# Sheet1.net
KiCad netlist of a schematic drawn in Altium Designer
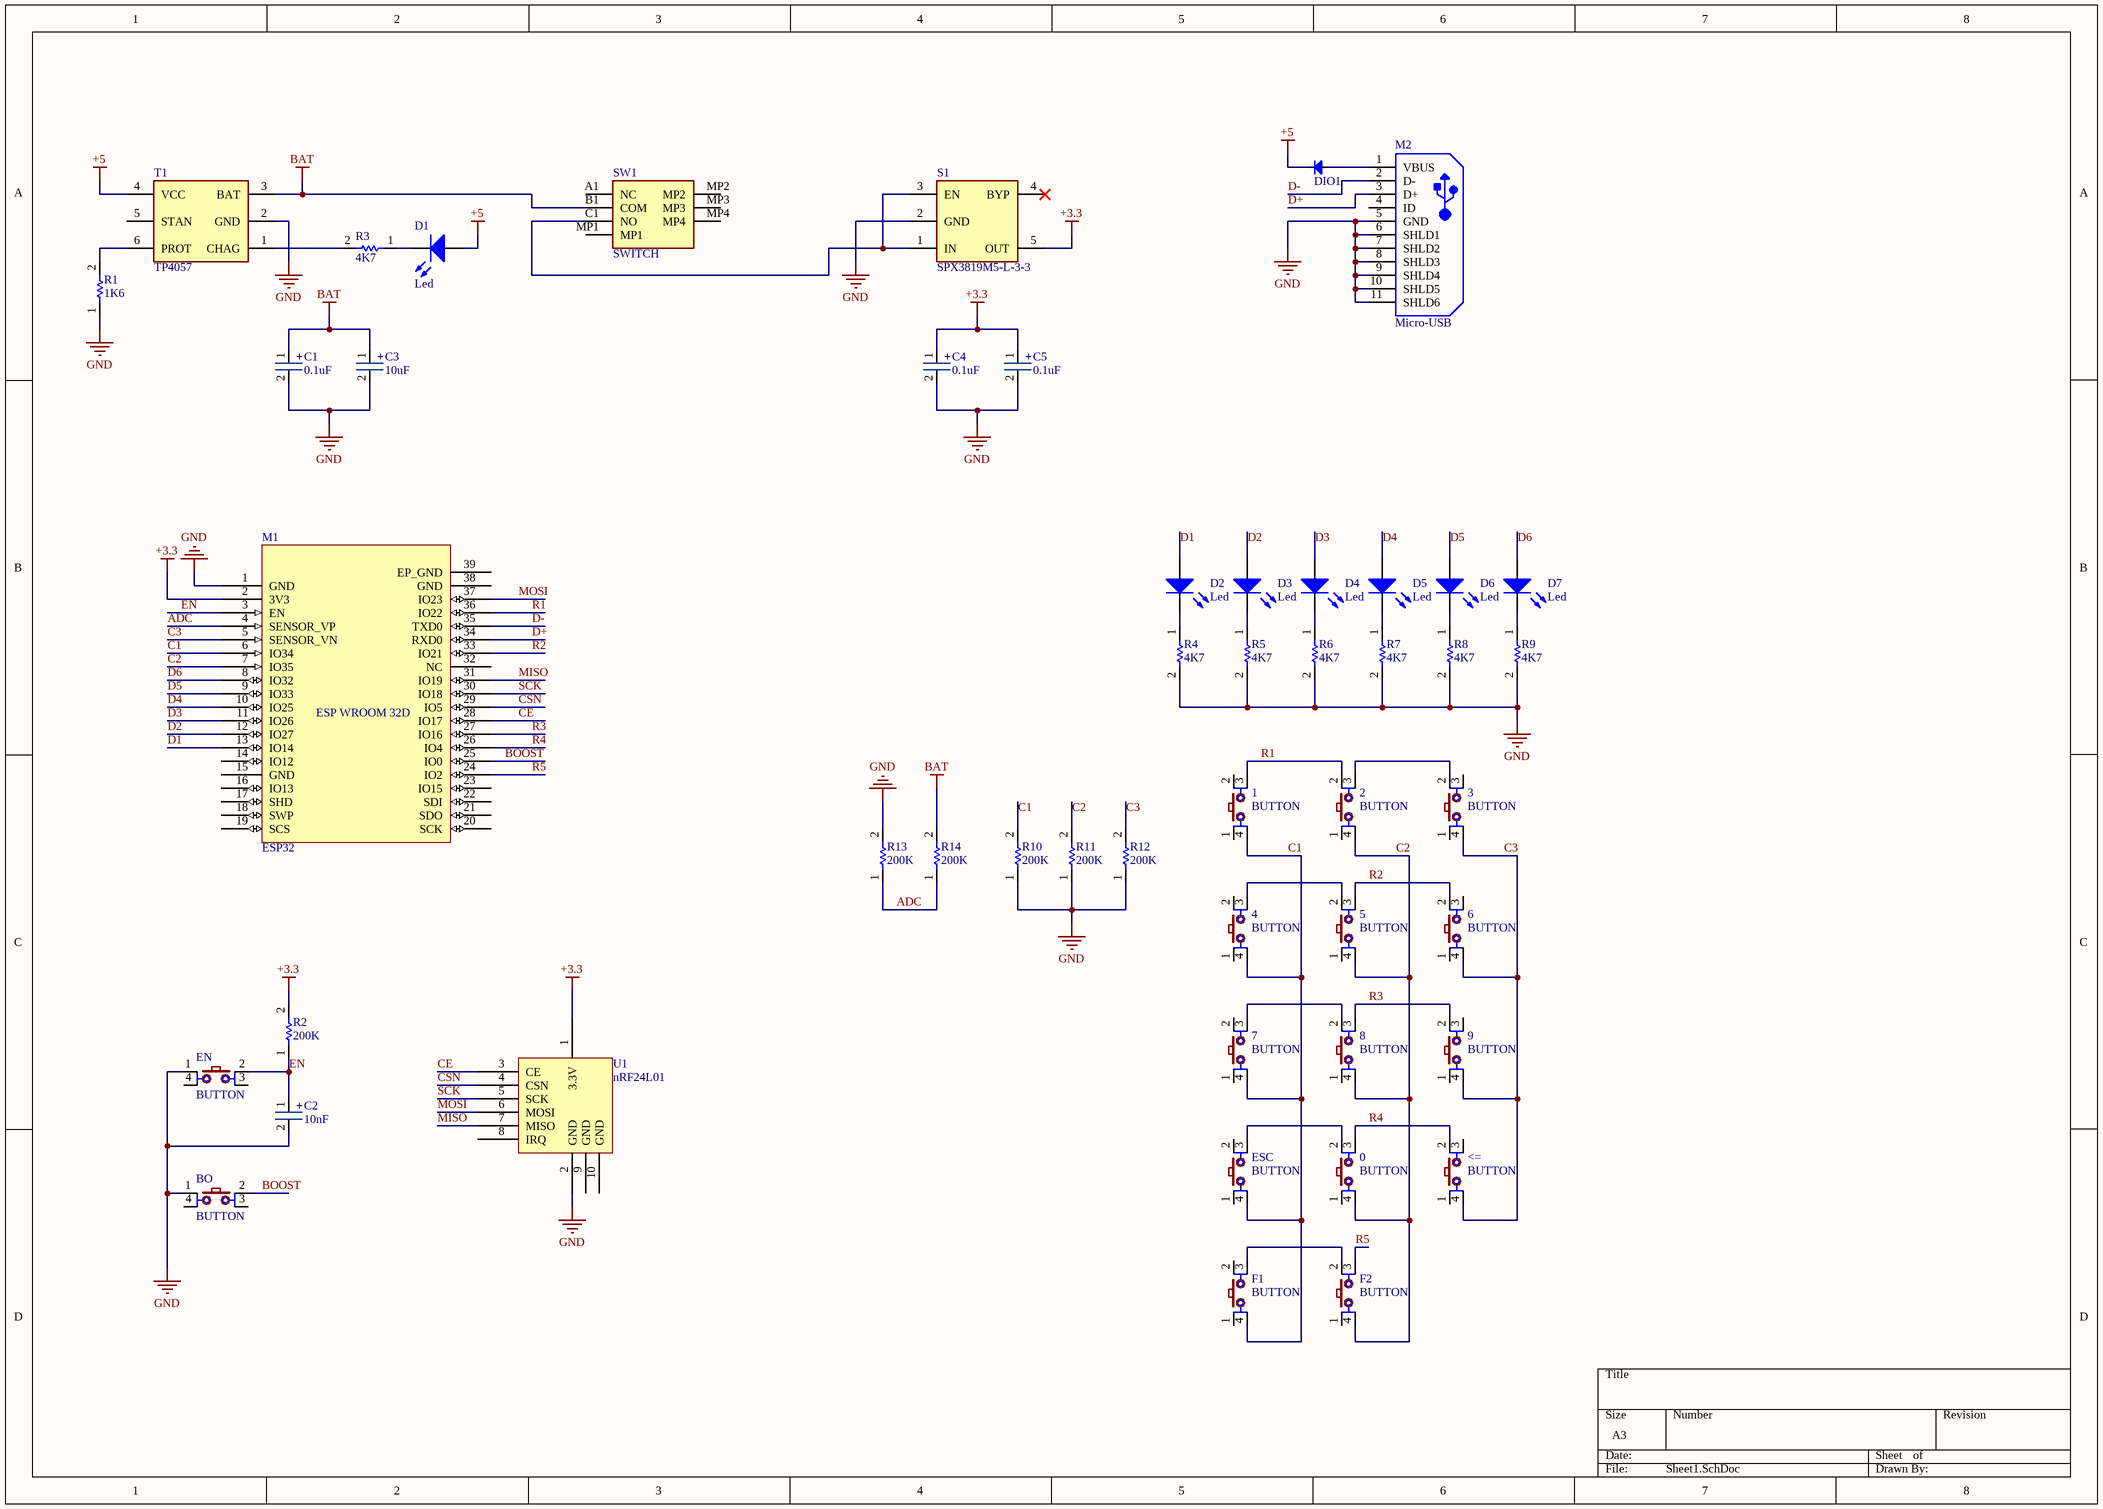
[diagram p0: Sheet1.SchDoc]

(export (version "E")
  (design (tool "Eeschema 10.0.6"))
  (components
    (comp (ref "0")
      (value "BUTTON")
      (footprint "BUTTON 4X4mm")
      (libsource (lib "Librarys") (part "BUTTON 4 PIN"))
    )
    (comp (ref "1")
      (value "BUTTON")
      (footprint "BUTTON 4X4mm")
      (libsource (lib "Librarys") (part "BUTTON 4 PIN"))
    )
    (comp (ref "2")
      (value "BUTTON")
      (footprint "BUTTON 4X4mm")
      (libsource (lib "Librarys") (part "BUTTON 4 PIN"))
    )
    (comp (ref "3")
      (value "BUTTON")
      (footprint "BUTTON 4X4mm")
      (libsource (lib "Librarys") (part "BUTTON 4 PIN"))
    )
    (comp (ref "4")
      (value "BUTTON")
      (footprint "BUTTON 4X4mm")
      (libsource (lib "Librarys") (part "BUTTON 4 PIN"))
    )
    (comp (ref "5")
      (value "BUTTON")
      (footprint "BUTTON 4X4mm")
      (libsource (lib "Librarys") (part "BUTTON 4 PIN"))
    )
    (comp (ref "6")
      (value "BUTTON")
      (footprint "BUTTON 4X4mm")
      (libsource (lib "Librarys") (part "BUTTON 4 PIN"))
    )
    (comp (ref "7")
      (value "BUTTON")
      (footprint "BUTTON 4X4mm")
      (libsource (lib "Librarys") (part "BUTTON 4 PIN"))
    )
    (comp (ref "8")
      (value "BUTTON")
      (footprint "BUTTON 4X4mm")
      (libsource (lib "Librarys") (part "BUTTON 4 PIN"))
    )
    (comp (ref "9")
      (value "BUTTON")
      (footprint "BUTTON 4X4mm")
      (libsource (lib "Librarys") (part "BUTTON 4 PIN"))
    )
    (comp (ref "<=")
      (value "BUTTON")
      (footprint "BUTTON 4X4mm")
      (libsource (lib "Librarys") (part "BUTTON 4 PIN"))
    )
    (comp (ref "BO")
      (value "BUTTON")
      (footprint "BUTTON 3x4mm 4PIN")
      (libsource (lib "Librarys") (part "BUTTON 4 PIN"))
    )
    (comp (ref "C1")
      (value "0.1uF")
      (footprint "Cap_0603_A")
      (description "General Purpose Ceramic Capacitor, 0603, 1nF, 10%, X7R, 15%, 50V")
      (fields (field (name "VOLTAGE") "50V") (field (name "TOLERANCE") "10%"))
      (libsource (lib "ResCapTransDio") (part "Capacitor"))
    )
    (comp (ref "C2")
      (value "10nF")
      (footprint "Cap_0603_A")
      (description "General Purpose Ceramic Capacitor, 0603, 1nF, 10%, X7R, 15%, 50V")
      (fields (field (name "VOLTAGE") "50V") (field (name "TOLERANCE") "10%"))
      (libsource (lib "ResCapTransDio") (part "Capacitor"))
    )
    (comp (ref "C3")
      (value "10uF")
      (footprint "Cap_0603_A")
      (description "General Purpose Ceramic Capacitor, 0603, 1nF, 10%, X7R, 15%, 50V")
      (fields (field (name "VOLTAGE") "50V") (field (name "TOLERANCE") "10%"))
      (libsource (lib "ResCapTransDio") (part "Capacitor"))
    )
    (comp (ref "C4")
      (value "0.1uF")
      (footprint "Cap_0603_A")
      (description "General Purpose Ceramic Capacitor, 0603, 1nF, 10%, X7R, 15%, 50V")
      (fields (field (name "VOLTAGE") "50V") (field (name "TOLERANCE") "10%"))
      (libsource (lib "ResCapTransDio") (part "Capacitor"))
    )
    (comp (ref "C5")
      (value "0.1uF")
      (footprint "Cap_0603_A")
      (description "General Purpose Ceramic Capacitor, 0603, 1nF, 10%, X7R, 15%, 50V")
      (fields (field (name "VOLTAGE") "50V") (field (name "TOLERANCE") "10%"))
      (libsource (lib "ResCapTransDio") (part "Capacitor"))
    )
    (comp (ref "D1") (value "Led") (footprint "LED 0603") (libsource (lib "ResCapTransDio") (part "Led")))
    (comp (ref "D2") (value "Led") (footprint "LED 0603") (libsource (lib "ResCapTransDio") (part "Led")))
    (comp (ref "D3") (value "Led") (footprint "LED 0603") (libsource (lib "ResCapTransDio") (part "Led")))
    (comp (ref "D4") (value "Led") (footprint "LED 0603") (libsource (lib "ResCapTransDio") (part "Led")))
    (comp (ref "D5") (value "Led") (footprint "LED 0603") (libsource (lib "ResCapTransDio") (part "Led")))
    (comp (ref "D6") (value "Led") (footprint "LED 0603") (libsource (lib "ResCapTransDio") (part "Led")))
    (comp (ref "D7") (value "Led") (footprint "LED 0603") (libsource (lib "ResCapTransDio") (part "Led")))
    (comp (ref "DIO1")
      (value "Diode SMD")
      (footprint "DIO-SMD-123")
      (description "Default Diode")
      (fields (field (name "PUBLISHER") "Altium Limited"))
      (libsource (lib "TechMT.VN_Lib_Project v2") (part "Diode SMD"))
    )
    (comp (ref "EN")
      (value "BUTTON")
      (footprint "BUTTON 3x4mm 4PIN")
      (libsource (lib "Librarys") (part "BUTTON 4 PIN"))
    )
    (comp (ref "ESC")
      (value "BUTTON")
      (footprint "BUTTON 4X4mm")
      (libsource (lib "Librarys") (part "BUTTON 4 PIN"))
    )
    (comp (ref "F1")
      (value "BUTTON")
      (footprint "BUTTON 4X4mm")
      (libsource (lib "Librarys") (part "BUTTON 4 PIN"))
    )
    (comp (ref "F2")
      (value "BUTTON")
      (footprint "BUTTON 4X4mm")
      (libsource (lib "Librarys") (part "BUTTON 4 PIN"))
    )
    (comp (ref "M1")
      (value "ESP32")
      (footprint "ESP32-WROOM-32D")
      (libsource (lib "ESP-WROOM-32D") (part "ESP32"))
    )
    (comp (ref "M2")
      (value "Micro-USB")
      (footprint "2.0 5 PIN SMD")
      (libsource (lib "Librarys") (part "Micro-USB"))
    )
    (comp (ref "R1")
      (value "1K6")
      (footprint "Res_0603")
      (libsource (lib "ResCapTransDio") (part "Resistor"))
    )
    (comp (ref "R2")
      (value "200K")
      (footprint "Res_0603")
      (libsource (lib "ResCapTransDio") (part "Resistor"))
    )
    (comp (ref "R3")
      (value "4K7")
      (footprint "Res_0603")
      (libsource (lib "ResCapTransDio") (part "Resistor"))
    )
    (comp (ref "R4")
      (value "4K7")
      (footprint "Res_0603")
      (libsource (lib "ResCapTransDio") (part "Resistor"))
    )
    (comp (ref "R5")
      (value "4K7")
      (footprint "Res_0603")
      (libsource (lib "ResCapTransDio") (part "Resistor"))
    )
    (comp (ref "R6")
      (value "4K7")
      (footprint "Res_0603")
      (libsource (lib "ResCapTransDio") (part "Resistor"))
    )
    (comp (ref "R7")
      (value "4K7")
      (footprint "Res_0603")
      (libsource (lib "ResCapTransDio") (part "Resistor"))
    )
    (comp (ref "R8")
      (value "4K7")
      (footprint "Res_0603")
      (libsource (lib "ResCapTransDio") (part "Resistor"))
    )
    (comp (ref "R9")
      (value "4K7")
      (footprint "Res_0603")
      (libsource (lib "ResCapTransDio") (part "Resistor"))
    )
    (comp (ref "R10")
      (value "200K")
      (footprint "Res_0603")
      (libsource (lib "ResCapTransDio") (part "Resistor"))
    )
    (comp (ref "R11")
      (value "200K")
      (footprint "Res_0603")
      (libsource (lib "ResCapTransDio") (part "Resistor"))
    )
    (comp (ref "R12")
      (value "200K")
      (footprint "Res_0603")
      (libsource (lib "ResCapTransDio") (part "Resistor"))
    )
    (comp (ref "R13")
      (value "200K")
      (footprint "Res_0603")
      (libsource (lib "ResCapTransDio") (part "Resistor"))
    )
    (comp (ref "R14")
      (value "200K")
      (footprint "Res_0603")
      (libsource (lib "ResCapTransDio") (part "Resistor"))
    )
    (comp (ref "S1")
      (value "SPX3819M5-L-3-3")
      (footprint "FP-C04-091-OT-IPC_A")
      (description "Regulator 250mA")
      (libsource (lib "Regulator") (part "SPX3819M5-L-3-3"))
    )
    (comp (ref "SW1") (value "SWITCH") (footprint "MSK12C02") (libsource (lib "Librarys") (part "SWITCH")))
    (comp (ref "T1") (value "TP4057") (footprint "TP4057") (libsource (lib "Librarys") (part "TP4057")))
    (comp (ref "U1")
      (value "nRF24L01")
      (footprint "NRF24L01 + PA SMD")
      (libsource (lib "MODULEs") (part "nRF24L01"))
    )
  )
  (nets
    (net (code "1") (name "+3.3") (class "Default")
      (node (ref "C4") (pin "1") (pinfunction "1_1") (pintype "passive"))
      (node (ref "C5") (pin "1") (pinfunction "1_1") (pintype "passive"))
      (node (ref "M1") (pin "2") (pinfunction "3V3_2") (pintype "passive"))
      (node (ref "R2") (pin "2") (pinfunction "2_2") (pintype "passive"))
      (node (ref "S1") (pin "5") (pinfunction "OUT_5") (pintype "passive"))
      (node (ref "U1") (pin "1") (pinfunction "3.3V_1") (pintype "passive"))
    )
    (net (code "2") (name "+5") (class "Default")
      (node (ref "D1") (pin "1") (pinfunction "A_1") (pintype "passive"))
      (node (ref "DIO1") (pin "2") (pinfunction "K_2") (pintype "passive"))
      (node (ref "T1") (pin "4") (pinfunction "VCC_4") (pintype "power_in"))
    )
    (net (code "3") (name "/ADC") (class "Default")
      (node (ref "M1") (pin "4") (pinfunction "SENSOR_VP_4") (pintype "input"))
      (node (ref "R13") (pin "1") (pinfunction "1_1") (pintype "passive"))
      (node (ref "R14") (pin "1") (pinfunction "1_1") (pintype "passive"))
    )
    (net (code "4") (name "/BOOST") (class "Default")
      (node (ref "BO") (pin "2") (pinfunction "2_2") (pintype "passive"))
      (node (ref "M1") (pin "25") (pinfunction "IO0_25") (pintype "bidirectional"))
    )
    (net (code "5") (name "/C1") (class "Default")
      (node (ref "1") (pin "4") (pinfunction "4_4") (pintype "passive"))
      (node (ref "4") (pin "4") (pinfunction "4_4") (pintype "passive"))
      (node (ref "7") (pin "4") (pinfunction "4_4") (pintype "passive"))
      (node (ref "ESC") (pin "4") (pinfunction "4_4") (pintype "passive"))
      (node (ref "F1") (pin "4") (pinfunction "4_4") (pintype "passive"))
      (node (ref "M1") (pin "6") (pinfunction "IO34_6") (pintype "input"))
      (node (ref "R10") (pin "2") (pinfunction "2_2") (pintype "passive"))
    )
    (net (code "6") (name "/C2") (class "Default")
      (node (ref "0") (pin "4") (pinfunction "4_4") (pintype "passive"))
      (node (ref "2") (pin "4") (pinfunction "4_4") (pintype "passive"))
      (node (ref "5") (pin "4") (pinfunction "4_4") (pintype "passive"))
      (node (ref "8") (pin "4") (pinfunction "4_4") (pintype "passive"))
      (node (ref "F2") (pin "4") (pinfunction "4_4") (pintype "passive"))
      (node (ref "M1") (pin "7") (pinfunction "IO35_7") (pintype "input"))
      (node (ref "R11") (pin "2") (pinfunction "2_2") (pintype "passive"))
    )
    (net (code "7") (name "/C3") (class "Default")
      (node (ref "3") (pin "4") (pinfunction "4_4") (pintype "passive"))
      (node (ref "6") (pin "4") (pinfunction "4_4") (pintype "passive"))
      (node (ref "9") (pin "4") (pinfunction "4_4") (pintype "passive"))
      (node (ref "<=") (pin "4") (pinfunction "4_4") (pintype "passive"))
      (node (ref "M1") (pin "5") (pinfunction "SENSOR_VN_5") (pintype "input"))
      (node (ref "R12") (pin "2") (pinfunction "2_2") (pintype "passive"))
    )
    (net (code "8") (name "/CE") (class "Default")
      (node (ref "M1") (pin "28") (pinfunction "IO17_28") (pintype "bidirectional"))
      (node (ref "U1") (pin "3") (pinfunction "CE_3") (pintype "passive"))
    )
    (net (code "9") (name "/CSN") (class "Default")
      (node (ref "M1") (pin "29") (pinfunction "IO5_29") (pintype "bidirectional"))
      (node (ref "U1") (pin "4") (pinfunction "CSN_4") (pintype "passive"))
    )
    (net (code "10") (name "/D+") (class "Default")
      (node (ref "M1") (pin "34") (pinfunction "RXD0_34") (pintype "bidirectional"))
      (node (ref "M2") (pin "3") (pinfunction "D+_3") (pintype "passive"))
    )
    (net (code "11") (name "/D-") (class "Default")
      (node (ref "M1") (pin "35") (pinfunction "TXD0_35") (pintype "bidirectional"))
      (node (ref "M2") (pin "2") (pinfunction "D-_2") (pintype "passive"))
    )
    (net (code "12") (name "/D1") (class "Default")
      (node (ref "D2") (pin "1") (pinfunction "A_1") (pintype "passive"))
      (node (ref "M1") (pin "13") (pinfunction "IO14_13") (pintype "bidirectional"))
    )
    (net (code "13") (name "/D2") (class "Default")
      (node (ref "D3") (pin "1") (pinfunction "A_1") (pintype "passive"))
      (node (ref "M1") (pin "12") (pinfunction "IO27_12") (pintype "bidirectional"))
    )
    (net (code "14") (name "/D3") (class "Default")
      (node (ref "D4") (pin "1") (pinfunction "A_1") (pintype "passive"))
      (node (ref "M1") (pin "11") (pinfunction "IO26_11") (pintype "bidirectional"))
    )
    (net (code "15") (name "/D4") (class "Default")
      (node (ref "D5") (pin "1") (pinfunction "A_1") (pintype "passive"))
      (node (ref "M1") (pin "10") (pinfunction "IO25_10") (pintype "bidirectional"))
    )
    (net (code "16") (name "/D5") (class "Default")
      (node (ref "D6") (pin "1") (pinfunction "A_1") (pintype "passive"))
      (node (ref "M1") (pin "9") (pinfunction "IO33_9") (pintype "bidirectional"))
    )
    (net (code "17") (name "/D6") (class "Default")
      (node (ref "D7") (pin "1") (pinfunction "A_1") (pintype "passive"))
      (node (ref "M1") (pin "8") (pinfunction "IO32_8") (pintype "bidirectional"))
    )
    (net (code "18") (name "/EN") (class "Default")
      (node (ref "C2") (pin "1") (pinfunction "1_1") (pintype "passive"))
      (node (ref "EN") (pin "2") (pinfunction "2_2") (pintype "passive"))
      (node (ref "M1") (pin "3") (pinfunction "EN_3") (pintype "input"))
      (node (ref "R2") (pin "1") (pinfunction "1_1") (pintype "passive"))
    )
    (net (code "19") (name "/MISO") (class "Default")
      (node (ref "M1") (pin "31") (pinfunction "IO19_31") (pintype "bidirectional"))
      (node (ref "U1") (pin "7") (pinfunction "MISO_7") (pintype "passive"))
    )
    (net (code "20") (name "/MOSI") (class "Default")
      (node (ref "M1") (pin "37") (pinfunction "IO23_37") (pintype "bidirectional"))
      (node (ref "U1") (pin "6") (pinfunction "MOSI_6") (pintype "passive"))
    )
    (net (code "21") (name "/R1") (class "Default")
      (node (ref "1") (pin "3") (pinfunction "3_3") (pintype "passive"))
      (node (ref "2") (pin "2") (pinfunction "2_2") (pintype "passive"))
      (node (ref "M1") (pin "36") (pinfunction "IO22_36") (pintype "bidirectional"))
    )
    (net (code "22") (name "/R2") (class "Default")
      (node (ref "5") (pin "3") (pinfunction "3_3") (pintype "passive"))
      (node (ref "6") (pin "2") (pinfunction "2_2") (pintype "passive"))
      (node (ref "M1") (pin "33") (pinfunction "IO21_33") (pintype "bidirectional"))
    )
    (net (code "23") (name "/R3") (class "Default")
      (node (ref "8") (pin "3") (pinfunction "3_3") (pintype "passive"))
      (node (ref "9") (pin "2") (pinfunction "2_2") (pintype "passive"))
      (node (ref "M1") (pin "27") (pinfunction "IO16_27") (pintype "bidirectional"))
    )
    (net (code "24") (name "/R4") (class "Default")
      (node (ref "0") (pin "3") (pinfunction "3_3") (pintype "passive"))
      (node (ref "<=") (pin "2") (pinfunction "2_2") (pintype "passive"))
      (node (ref "M1") (pin "26") (pinfunction "IO4_26") (pintype "bidirectional"))
    )
    (net (code "25") (name "/R5") (class "Default")
      (node (ref "F2") (pin "3") (pinfunction "3_3") (pintype "passive"))
      (node (ref "M1") (pin "24") (pinfunction "IO2_24") (pintype "bidirectional"))
    )
    (net (code "26") (name "/SCK") (class "Default")
      (node (ref "M1") (pin "30") (pinfunction "IO18_30") (pintype "bidirectional"))
      (node (ref "U1") (pin "5") (pinfunction "SCK_5") (pintype "passive"))
    )
    (net (code "27") (name "BAT") (class "Default")
      (node (ref "C1") (pin "1") (pinfunction "1_1") (pintype "passive"))
      (node (ref "C3") (pin "1") (pinfunction "1_1") (pintype "passive"))
      (node (ref "R14") (pin "2") (pinfunction "2_2") (pintype "passive"))
      (node (ref "SW1") (pin "B1") (pinfunction "COM_B1") (pintype "passive"))
      (node (ref "T1") (pin "3") (pinfunction "BAT_3") (pintype "power_in"))
    )
    (net (code "28") (name "GND") (class "Default")
      (node (ref "BO") (pin "1") (pintype "passive"))
      (node (ref "C1") (pin "2") (pinfunction "2_2") (pintype "passive"))
      (node (ref "C2") (pin "2") (pinfunction "2_2") (pintype "passive"))
      (node (ref "C3") (pin "2") (pinfunction "2_2") (pintype "passive"))
      (node (ref "C4") (pin "2") (pinfunction "2_2") (pintype "passive"))
      (node (ref "C5") (pin "2") (pinfunction "2_2") (pintype "passive"))
      (node (ref "EN") (pin "1") (pintype "passive"))
      (node (ref "M1") (pin "1") (pinfunction "GND_1") (pintype "passive"))
      (node (ref "M2") (pin "10") (pinfunction "SHLD5_10") (pintype "passive"))
      (node (ref "M2") (pin "11") (pinfunction "SHLD6_11") (pintype "passive"))
      (node (ref "M2") (pin "5") (pinfunction "GND_5") (pintype "passive"))
      (node (ref "M2") (pin "6") (pinfunction "SHLD1_6") (pintype "passive"))
      (node (ref "M2") (pin "7") (pinfunction "SHLD2_7") (pintype "passive"))
      (node (ref "M2") (pin "8") (pinfunction "SHLD3_8") (pintype "passive"))
      (node (ref "M2") (pin "9") (pinfunction "SHLD4_9") (pintype "passive"))
      (node (ref "R1") (pin "1") (pinfunction "1_1") (pintype "passive"))
      (node (ref "R10") (pin "1") (pinfunction "1_1") (pintype "passive"))
      (node (ref "R11") (pin "1") (pinfunction "1_1") (pintype "passive"))
      (node (ref "R12") (pin "1") (pinfunction "1_1") (pintype "passive"))
      (node (ref "R13") (pin "2") (pinfunction "2_2") (pintype "passive"))
      (node (ref "R4") (pin "2") (pinfunction "2_2") (pintype "passive"))
      (node (ref "R5") (pin "2") (pinfunction "2_2") (pintype "passive"))
      (node (ref "R6") (pin "2") (pinfunction "2_2") (pintype "passive"))
      (node (ref "R7") (pin "2") (pinfunction "2_2") (pintype "passive"))
      (node (ref "R8") (pin "2") (pinfunction "2_2") (pintype "passive"))
      (node (ref "R9") (pin "2") (pinfunction "2_2") (pintype "passive"))
      (node (ref "S1") (pin "2") (pinfunction "GND_2") (pintype "passive"))
      (node (ref "T1") (pin "2") (pinfunction "GND_2") (pintype "passive"))
      (node (ref "U1") (pin "2") (pinfunction "GND_2") (pintype "passive"))
    )
    (net (code "29") (name "Net-(0-Pad2)") (class "Default")
      (node (ref "0") (pin "2") (pinfunction "2_2") (pintype "passive"))
      (node (ref "ESC") (pin "3") (pinfunction "3_3") (pintype "passive"))
    )
    (net (code "30") (name "Net-(2-Pad3)") (class "Default")
      (node (ref "2") (pin "3") (pinfunction "3_3") (pintype "passive"))
      (node (ref "3") (pin "2") (pinfunction "2_2") (pintype "passive"))
    )
    (net (code "31") (name "Net-(4-Pad3)") (class "Default")
      (node (ref "4") (pin "3") (pinfunction "3_3") (pintype "passive"))
      (node (ref "5") (pin "2") (pinfunction "2_2") (pintype "passive"))
    )
    (net (code "32") (name "Net-(7-Pad3)") (class "Default")
      (node (ref "7") (pin "3") (pinfunction "3_3") (pintype "passive"))
      (node (ref "8") (pin "2") (pinfunction "2_2") (pintype "passive"))
    )
    (net (code "33") (name "Net-(D1-K)") (class "Default")
      (node (ref "D1") (pin "2") (pinfunction "K_2") (pintype "passive"))
      (node (ref "R3") (pin "1") (pinfunction "1_1") (pintype "passive"))
    )
    (net (code "34") (name "Net-(D2-K)") (class "Default")
      (node (ref "D2") (pin "2") (pinfunction "K_2") (pintype "passive"))
      (node (ref "R4") (pin "1") (pinfunction "1_1") (pintype "passive"))
    )
    (net (code "35") (name "Net-(D3-K)") (class "Default")
      (node (ref "D3") (pin "2") (pinfunction "K_2") (pintype "passive"))
      (node (ref "R5") (pin "1") (pinfunction "1_1") (pintype "passive"))
    )
    (net (code "36") (name "Net-(D4-K)") (class "Default")
      (node (ref "D4") (pin "2") (pinfunction "K_2") (pintype "passive"))
      (node (ref "R6") (pin "1") (pinfunction "1_1") (pintype "passive"))
    )
    (net (code "37") (name "Net-(D5-K)") (class "Default")
      (node (ref "D5") (pin "2") (pinfunction "K_2") (pintype "passive"))
      (node (ref "R7") (pin "1") (pinfunction "1_1") (pintype "passive"))
    )
    (net (code "38") (name "Net-(D6-K)") (class "Default")
      (node (ref "D6") (pin "2") (pinfunction "K_2") (pintype "passive"))
      (node (ref "R8") (pin "1") (pinfunction "1_1") (pintype "passive"))
    )
    (net (code "39") (name "Net-(D7-K)") (class "Default")
      (node (ref "D7") (pin "2") (pinfunction "K_2") (pintype "passive"))
      (node (ref "R9") (pin "1") (pinfunction "1_1") (pintype "passive"))
    )
    (net (code "40") (name "Net-(DIO1-A)") (class "Default")
      (node (ref "DIO1") (pin "1") (pinfunction "A_1") (pintype "passive"))
      (node (ref "M2") (pin "1") (pinfunction "VBUS_1") (pintype "passive"))
    )
    (net (code "41") (name "Net-(F1-Pad3)") (class "Default")
      (node (ref "F1") (pin "3") (pinfunction "3_3") (pintype "passive"))
      (node (ref "F2") (pin "2") (pinfunction "2_2") (pintype "passive"))
    )
    (net (code "42") (name "Net-(S1-EN)") (class "Default")
      (node (ref "S1") (pin "1") (pinfunction "IN_1") (pintype "power_in"))
      (node (ref "S1") (pin "3") (pinfunction "EN_3") (pintype "power_in"))
      (node (ref "SW1") (pin "C1") (pinfunction "NO_C1") (pintype "passive"))
    )
    (net (code "43") (name "Net-(T1-CHAG)") (class "Default")
      (node (ref "R3") (pin "2") (pinfunction "2_2") (pintype "passive"))
      (node (ref "T1") (pin "1") (pinfunction "CHAG_1") (pintype "power_in"))
    )
    (net (code "44") (name "Net-(T1-PROT)") (class "Default")
      (node (ref "R1") (pin "2") (pinfunction "2_2") (pintype "passive"))
      (node (ref "T1") (pin "6") (pinfunction "PROT_6") (pintype "passive"))
    )
    (net (code "45") (name "unconnected-(0-Pad1)") (class "Default")
      (node (ref "0") (pin "1") (pintype "passive"))
    )
    (net (code "46") (name "unconnected-(1-Pad1)") (class "Default")
      (node (ref "1") (pin "1") (pintype "passive"))
    )
    (net (code "47") (name "unconnected-(1-Pad2)") (class "Default")
      (node (ref "1") (pin "2") (pinfunction "2_2") (pintype "passive"))
    )
    (net (code "48") (name "unconnected-(2-Pad1)") (class "Default")
      (node (ref "2") (pin "1") (pintype "passive"))
    )
    (net (code "49") (name "unconnected-(3-Pad1)") (class "Default")
      (node (ref "3") (pin "1") (pintype "passive"))
    )
    (net (code "50") (name "unconnected-(3-Pad3)") (class "Default")
      (node (ref "3") (pin "3") (pinfunction "3_3") (pintype "passive"))
    )
    (net (code "51") (name "unconnected-(4-Pad1)") (class "Default")
      (node (ref "4") (pin "1") (pintype "passive"))
    )
    (net (code "52") (name "unconnected-(4-Pad2)") (class "Default")
      (node (ref "4") (pin "2") (pinfunction "2_2") (pintype "passive"))
    )
    (net (code "53") (name "unconnected-(5-Pad1)") (class "Default")
      (node (ref "5") (pin "1") (pintype "passive"))
    )
    (net (code "54") (name "unconnected-(6-Pad1)") (class "Default")
      (node (ref "6") (pin "1") (pintype "passive"))
    )
    (net (code "55") (name "unconnected-(6-Pad3)") (class "Default")
      (node (ref "6") (pin "3") (pinfunction "3_3") (pintype "passive"))
    )
    (net (code "56") (name "unconnected-(7-Pad1)") (class "Default")
      (node (ref "7") (pin "1") (pintype "passive"))
    )
    (net (code "57") (name "unconnected-(7-Pad2)") (class "Default")
      (node (ref "7") (pin "2") (pinfunction "2_2") (pintype "passive"))
    )
    (net (code "58") (name "unconnected-(8-Pad1)") (class "Default")
      (node (ref "8") (pin "1") (pintype "passive"))
    )
    (net (code "59") (name "unconnected-(9-Pad1)") (class "Default")
      (node (ref "9") (pin "1") (pintype "passive"))
    )
    (net (code "60") (name "unconnected-(9-Pad3)") (class "Default")
      (node (ref "9") (pin "3") (pinfunction "3_3") (pintype "passive"))
    )
    (net (code "61") (name "unconnected-(<=-Pad1)") (class "Default")
      (node (ref "<=") (pin "1") (pintype "passive"))
    )
    (net (code "62") (name "unconnected-(<=-Pad3)") (class "Default")
      (node (ref "<=") (pin "3") (pinfunction "3_3") (pintype "passive"))
    )
    (net (code "63") (name "unconnected-(BO-Pad3)") (class "Default")
      (node (ref "BO") (pin "3") (pinfunction "3_3") (pintype "passive"))
    )
    (net (code "64") (name "unconnected-(BO-Pad4)") (class "Default")
      (node (ref "BO") (pin "4") (pinfunction "4_4") (pintype "passive"))
    )
    (net (code "65") (name "unconnected-(EN-Pad3)") (class "Default")
      (node (ref "EN") (pin "3") (pinfunction "3_3") (pintype "passive"))
    )
    (net (code "66") (name "unconnected-(EN-Pad4)") (class "Default")
      (node (ref "EN") (pin "4") (pinfunction "4_4") (pintype "passive"))
    )
    (net (code "67") (name "unconnected-(ESC-Pad1)") (class "Default")
      (node (ref "ESC") (pin "1") (pintype "passive"))
    )
    (net (code "68") (name "unconnected-(ESC-Pad2)") (class "Default")
      (node (ref "ESC") (pin "2") (pinfunction "2_2") (pintype "passive"))
    )
    (net (code "69") (name "unconnected-(F1-Pad1)") (class "Default")
      (node (ref "F1") (pin "1") (pintype "passive"))
    )
    (net (code "70") (name "unconnected-(F1-Pad2)") (class "Default")
      (node (ref "F1") (pin "2") (pinfunction "2_2") (pintype "passive"))
    )
    (net (code "71") (name "unconnected-(F2-Pad1)") (class "Default")
      (node (ref "F2") (pin "1") (pintype "passive"))
    )
    (net (code "72") (name "unconnected-(M1-EP_GND-Pad39)") (class "Default")
      (node (ref "M1") (pin "39") (pinfunction "EP_GND_39") (pintype "passive"))
    )
    (net (code "73") (name "unconnected-(M1-GND-Pad15)") (class "Default")
      (node (ref "M1") (pin "15") (pinfunction "GND_15") (pintype "passive"))
    )
    (net (code "74") (name "unconnected-(M1-GND-Pad38)") (class "Default")
      (node (ref "M1") (pin "38") (pinfunction "GND_38") (pintype "passive"))
    )
    (net (code "75") (name "unconnected-(M1-IO12-Pad14)") (class "Default")
      (node (ref "M1") (pin "14") (pinfunction "IO12_14") (pintype "bidirectional"))
    )
    (net (code "76") (name "unconnected-(M1-IO13-Pad16)") (class "Default")
      (node (ref "M1") (pin "16") (pinfunction "IO13_16") (pintype "bidirectional"))
    )
    (net (code "77") (name "unconnected-(M1-IO15-Pad23)") (class "Default")
      (node (ref "M1") (pin "23") (pinfunction "IO15_23") (pintype "bidirectional"))
    )
    (net (code "78") (name "unconnected-(M1-NC-Pad32)") (class "Default")
      (node (ref "M1") (pin "32") (pinfunction "NC_32") (pintype "passive"))
    )
    (net (code "79") (name "unconnected-(M1-SCK-Pad20)") (class "Default")
      (node (ref "M1") (pin "20") (pinfunction "SCK_20") (pintype "bidirectional"))
    )
    (net (code "80") (name "unconnected-(M1-SCS-Pad19)") (class "Default")
      (node (ref "M1") (pin "19") (pinfunction "SCS_19") (pintype "bidirectional"))
    )
    (net (code "81") (name "unconnected-(M1-SDI-Pad22)") (class "Default")
      (node (ref "M1") (pin "22") (pinfunction "SDI_22") (pintype "bidirectional"))
    )
    (net (code "82") (name "unconnected-(M1-SDO-Pad21)") (class "Default")
      (node (ref "M1") (pin "21") (pinfunction "SDO_21") (pintype "bidirectional"))
    )
    (net (code "83") (name "unconnected-(M1-SHD-Pad17)") (class "Default")
      (node (ref "M1") (pin "17") (pinfunction "SHD_17") (pintype "bidirectional"))
    )
    (net (code "84") (name "unconnected-(M1-SWP-Pad18)") (class "Default")
      (node (ref "M1") (pin "18") (pinfunction "SWP_18") (pintype "bidirectional"))
    )
    (net (code "85") (name "unconnected-(M2-ID-Pad4)") (class "Default")
      (node (ref "M2") (pin "4") (pinfunction "ID_4") (pintype "passive"))
    )
    (net (code "86") (name "unconnected-(S1-BYP-Pad4)") (class "Default")
      (node (ref "S1") (pin "4") (pinfunction "BYP_4") (pintype "power_in+no_connect"))
    )
    (net (code "87") (name "unconnected-(SW1-NC-PadA1)") (class "Default")
      (node (ref "SW1") (pin "A1") (pinfunction "NC_A1") (pintype "passive"))
    )
    (net (code "88") (name "unconnected-(SW1-PadMP1)") (class "Default")
      (node (ref "SW1") (pin "MP1") (pinfunction "MP1_MP1") (pintype "passive"))
    )
    (net (code "89") (name "unconnected-(SW1-PadMP2)") (class "Default")
      (node (ref "SW1") (pin "MP2") (pinfunction "MP2_MP2") (pintype "passive"))
    )
    (net (code "90") (name "unconnected-(SW1-PadMP3)") (class "Default")
      (node (ref "SW1") (pin "MP3") (pinfunction "MP3_MP3") (pintype "passive"))
    )
    (net (code "91") (name "unconnected-(SW1-PadMP4)") (class "Default")
      (node (ref "SW1") (pin "MP4") (pinfunction "MP4_MP4") (pintype "passive"))
    )
    (net (code "92") (name "unconnected-(T1-STAN-Pad5)") (class "Default")
      (node (ref "T1") (pin "5") (pinfunction "STAN_5") (pintype "passive"))
    )
    (net (code "93") (name "unconnected-(U1-GND-Pad9)") (class "Default")
      (node (ref "U1") (pin "9") (pinfunction "GND_9") (pintype "passive"))
    )
    (net (code "94") (name "unconnected-(U1-GND-Pad10)") (class "Default")
      (node (ref "U1") (pin "10") (pinfunction "GND_10") (pintype "passive"))
    )
    (net (code "95") (name "unconnected-(U1-IRQ-Pad8)") (class "Default")
      (node (ref "U1") (pin "8") (pinfunction "IRQ_8") (pintype "passive"))
    )
  )
)
